# Main.net
KiCad netlist of a schematic drawn in Altium Designer
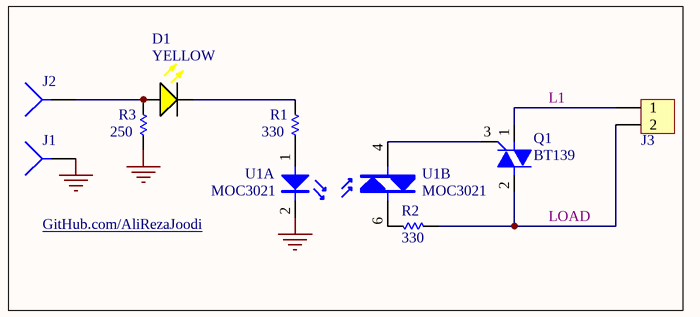
[diagram p0: Main.SchDoc]

(export (version "E")
  (design (tool "Eeschema 10.0.6"))
  (components
    (comp (ref "D1")
      (value "YELLOW")
      (footprint "LED_THD_5MM_YELLOW")
      (description "LED, Yellow")
      (fields (field (name "MANUFACTURER") "Generic Components") (field (name "PUBLISHER") "Altium Limited"))
      (libsource (lib "Display") (part "LED_YELLOW"))
    )
    (comp (ref "J1")
      (value "1PIN")
      (footprint "TestPoint_THD_A")
      (description "Connector, Socket, 1Pin")
      (libsource (lib "Connector") (part "Connector_Socket_1Pin_Female"))
    )
    (comp (ref "J2")
      (value "1PIN")
      (footprint "TestPoint_THD_A")
      (description "Connector, Socket, 1Pin")
      (libsource (lib "Connector") (part "Connector_Socket_1Pin_Female"))
    )
    (comp (ref "J3")
      (value "2PIN")
      (footprint "Connector_Phoenix_2PIN_MSTB")
      (description "Connector, Header, 2Pin")
      (libsource (lib "Connector") (part "Connector_Header_2Pin"))
    )
    (comp (ref "Q1")
      (value "BT139")
      (footprint "TO220_3PIN_V")
      (description "Triac,")
      (libsource (lib "Passive") (part "Triac"))
    )
    (comp (ref "R1")
      (value "330")
      (footprint "R_SMD_0805_EXPANDED")
      (description "Resistor")
      (libsource (lib "Passive") (part "Resistor"))
    )
    (comp (ref "R2")
      (value "330")
      (footprint "R_SMD_0805_EXPANDED")
      (description "Resistor")
      (libsource (lib "Passive") (part "Resistor"))
    )
    (comp (ref "R3")
      (value "250")
      (footprint "R_THD_AXIAL0.4(1/4W)")
      (description "Resistor")
      (libsource (lib "Passive") (part "Resistor"))
    )
    (comp (ref "U1")
      (value "MOC3021")
      (footprint "DIP_6")
      (description "Opto-Triac")
      (libsource (lib "Other_Myself") (part "MOC3021"))
    )
  )
  (nets
    (net (code "1") (name "/L1") (class "Default")
      (node (ref "J3") (pin "1") (pinfunction "1_1") (pintype "passive"))
      (node (ref "Q1") (pin "1") (pinfunction "T1_1") (pintype "passive"))
    )
    (net (code "2") (name "/LOAD") (class "Default")
      (node (ref "J3") (pin "2") (pinfunction "2_2") (pintype "passive"))
      (node (ref "Q1") (pin "2") (pinfunction "T2_2") (pintype "passive"))
      (node (ref "R2") (pin "2") (pinfunction "2_2") (pintype "passive"))
    )
    (net (code "3") (name "GND") (class "Default")
      (node (ref "J1") (pin "1") (pinfunction "A_1") (pintype "passive"))
      (node (ref "R3") (pin "2") (pinfunction "2_2") (pintype "passive"))
      (node (ref "U1") (pin "2") (pinfunction "K_2") (pintype "power_in"))
    )
    (net (code "4") (name "Net-(D1-A)") (class "Default")
      (node (ref "D1") (pin "1") (pinfunction "A_1") (pintype "passive"))
      (node (ref "J2") (pin "1") (pinfunction "A_1") (pintype "passive"))
      (node (ref "R3") (pin "1") (pinfunction "1_1") (pintype "passive"))
    )
    (net (code "5") (name "Net-(D1-K)") (class "Default")
      (node (ref "D1") (pin "2") (pinfunction "K_2") (pintype "passive"))
      (node (ref "R1") (pin "1") (pinfunction "1_1") (pintype "passive"))
    )
    (net (code "6") (name "Net-(Q1-G)") (class "Default")
      (node (ref "Q1") (pin "3") (pinfunction "G_3") (pintype "passive"))
      (node (ref "U1") (pin "4") (pinfunction "A/K_4") (pintype "passive"))
    )
    (net (code "7") (name "Net-(R2-Pad1)") (class "Default")
      (node (ref "R2") (pin "1") (pinfunction "1_1") (pintype "passive"))
      (node (ref "U1") (pin "6") (pinfunction "A/K_6") (pintype "passive"))
    )
    (net (code "8") (name "Net-(U1A-A)") (class "Default")
      (node (ref "R1") (pin "2") (pinfunction "2_2") (pintype "passive"))
      (node (ref "U1") (pin "1") (pinfunction "A_1") (pintype "power_in"))
    )
  )
)
